# board.net
KiCad netlist of a schematic drawn in EAGLE
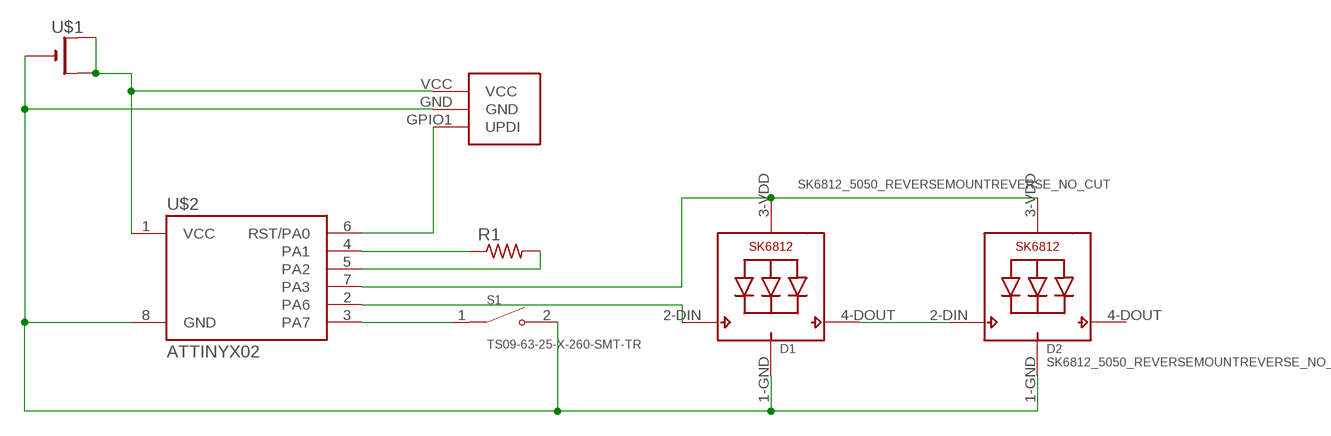
[diagram p0: schematic, sheet 1]

(export (version "E")
  (design (tool "Eeschema 10.0.6"))
  (components
    (comp (ref "D1")
      (value "SK6812_5050_REVERSEMOUNTREVERSE_NO_CUT")
      (footprint "eagle-import:SK6812_REVERSE_NO_CUT")
      (libsource (lib "eagle-import") (part "SK6812_5050_REVERSEMOUNTREVERSE_NO_CUT"))
    )
    (comp (ref "D2")
      (value "SK6812_5050_REVERSEMOUNTREVERSE_NO_CUT")
      (footprint "eagle-import:SK6812_REVERSE_NO_CUT")
      (libsource (lib "eagle-import") (part "SK6812_5050_REVERSEMOUNTREVERSE_NO_CUT"))
    )
    (comp (ref "R1")
      (value "R-US_R1206")
      (footprint "eagle-import:R1206")
      (libsource (lib "eagle-import") (part "R-US_R1206"))
    )
    (comp (ref "S1")
      (value "TS09-63-25-X-260-SMT-TR")
      (footprint "eagle-import:SW_TS09-63-25-X-260-SMT-TR")
      (fields (field (name "MANUFACTURER") "CUI Devices"))
      (libsource (lib "eagle-import") (part "TS09-63-25-X-260-SMT-TR"))
    )
    (comp (ref "U$1")
      (value "CR2032SMT")
      (footprint "eagle-import:CR2032-SMD")
      (libsource (lib "eagle-import") (part "CR2032SMT"))
    )
    (comp (ref "U$2")
      (value "ATTINYX02")
      (footprint "eagle-import:SOIC08_JEDEC_150MIL")
      (libsource (lib "eagle-import") (part "ATTINYX02"))
    )
    (comp (ref "U$3")
      (value "SAO")
      (footprint "eagle-import:SAO_SMD")
      (libsource (lib "eagle-import") (part "SAO"))
    )
  )
  (nets
    (net (code "1") (name "Net-(D1-DI)") (class "Default")
      (node (ref "D1") (pin "2-DIN") (pinfunction "DI_2-DIN") (pintype "input"))
      (node (ref "U$2") (pin "2") (pinfunction "PA6_2") (pintype "bidirectional"))
    )
    (net (code "2") (name "Net-(D1-DO)") (class "Default")
      (node (ref "D1") (pin "4-DOUT") (pinfunction "DO_4-DOUT") (pintype "output"))
      (node (ref "D2") (pin "2-DIN") (pinfunction "DI_2-DIN") (pintype "input"))
    )
    (net (code "3") (name "Net-(D1-GND)") (class "Default")
      (node (ref "D1") (pin "1-GND") (pinfunction "GND_1-GND") (pintype "power_in"))
      (node (ref "D2") (pin "1-GND") (pinfunction "GND_1-GND") (pintype "power_in"))
      (node (ref "S1") (pin "2") (pinfunction "2_2") (pintype "passive"))
      (node (ref "U$1") (pin "-") (pinfunction "-_-") (pintype "passive"))
      (node (ref "U$2") (pin "8") (pinfunction "GND_8") (pintype "power_in"))
      (node (ref "U$3") (pin "GND") (pinfunction "GND_GND") (pintype "bidirectional"))
    )
    (net (code "4") (name "Net-(D1-VDD)") (class "Default")
      (node (ref "D1") (pin "3-VDD") (pinfunction "VDD_3-VDD") (pintype "power_in"))
      (node (ref "D2") (pin "3-VDD") (pinfunction "VDD_3-VDD") (pintype "power_in"))
      (node (ref "U$2") (pin "7") (pinfunction "PA3_7") (pintype "bidirectional"))
    )
    (net (code "5") (name "Net-(U$1-+)") (class "Default")
      (node (ref "U$1") (pin "+$1") (pinfunction "+_+$1") (pintype "passive"))
      (node (ref "U$1") (pin "+$2") (pinfunction "+1_+$2") (pintype "passive"))
      (node (ref "U$2") (pin "1") (pinfunction "VCC_1") (pintype "power_in"))
      (node (ref "U$3") (pin "VCC") (pinfunction "VCC_VCC") (pintype "bidirectional"))
    )
    (net (code "6") (name "Net-(U$2-PA1)") (class "Default")
      (node (ref "R1") (pin "1") (pinfunction "1_1") (pintype "passive"))
      (node (ref "U$2") (pin "4") (pinfunction "PA1_4") (pintype "bidirectional"))
    )
    (net (code "7") (name "Net-(U$2-PA2)") (class "Default")
      (node (ref "R1") (pin "2") (pinfunction "2_2") (pintype "passive"))
      (node (ref "U$2") (pin "5") (pinfunction "PA2_5") (pintype "bidirectional"))
    )
    (net (code "8") (name "Net-(U$2-PA7)") (class "Default")
      (node (ref "S1") (pin "1") (pinfunction "1_1") (pintype "passive"))
      (node (ref "U$2") (pin "3") (pinfunction "PA7_3") (pintype "bidirectional"))
    )
    (net (code "9") (name "Net-(U$2-RST{slash}PA0)") (class "Default")
      (node (ref "U$2") (pin "6") (pinfunction "RST/PA0_6") (pintype "bidirectional"))
      (node (ref "U$3") (pin "GPIO1") (pinfunction "UPDI_GPIO1") (pintype "bidirectional"))
    )
    (net (code "10") (name "unconnected-(D2-DO-Pad4-DOUT)") (class "Default")
      (node (ref "D2") (pin "4-DOUT") (pinfunction "DO_4-DOUT") (pintype "output"))
    )
  )
)
